# Arduino_lcd.net
KiCad netlist of a schematic drawn in EAGLE
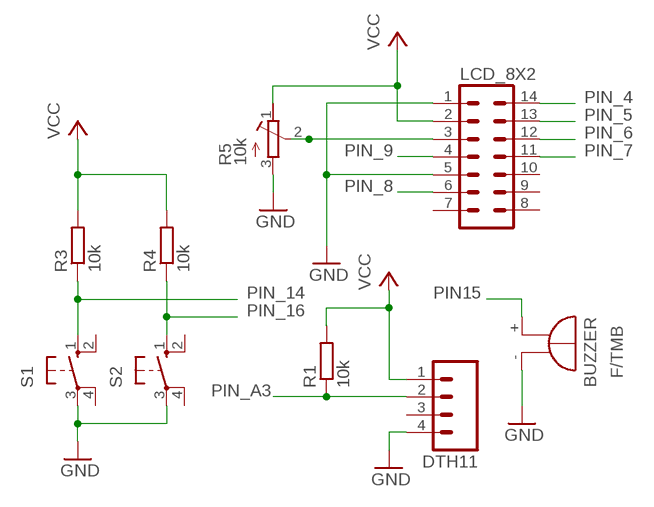
[diagram p0: schematic, sheet 1]

(export (version "E")
  (design (tool "Eeschema 10.0.6"))
  (components
    (comp (ref "BUZZER")
      (value "F/TMB")
      (footprint "eagle-import:F_TMB")
      (libsource (lib "eagle-import") (part "F/TMB"))
    )
    (comp (ref "DTH11")
      (value "M04")
      (footprint "eagle-import:04P")
      (libsource (lib "eagle-import") (part "M04"))
    )
    (comp (ref "LCD_8X2")
      (value "IC14P")
      (footprint "eagle-import:IC14P")
      (libsource (lib "eagle-import") (part "IC14P"))
    )
    (comp (ref "R1")
      (value "10k")
      (footprint "eagle-import:0207_10")
      (libsource (lib "eagle-import") (part "R-EU_0207/10"))
    )
    (comp (ref "R3")
      (value "10k")
      (footprint "eagle-import:0207_10")
      (libsource (lib "eagle-import") (part "R-EU_0207/10"))
    )
    (comp (ref "R4")
      (value "10k")
      (footprint "eagle-import:0207_10")
      (libsource (lib "eagle-import") (part "R-EU_0207/10"))
    )
    (comp (ref "R5")
      (value "10k")
      (footprint "eagle-import:RTRIM3314J")
      (libsource (lib "eagle-import") (part "R-TRIMM3314J"))
    )
    (comp (ref "S1")
      (value "10-XX")
      (footprint "eagle-import:B3F-10XX")
      (fields (field (name "MPN") "B3F-1000"))
      (libsource (lib "eagle-import") (part "10-XX"))
    )
    (comp (ref "S2")
      (value "10-XX")
      (footprint "eagle-import:B3F-10XX")
      (fields (field (name "MPN") "B3F-1000"))
      (libsource (lib "eagle-import") (part "10-XX"))
    )
  )
  (nets
    (net (code "1") (name "/PIN15") (class "Default")
      (node (ref "BUZZER") (pin "+") (pinfunction "+_+") (pintype "passive"))
    )
    (net (code "2") (name "/PIN_4") (class "Default")
      (node (ref "LCD_8X2") (pin "14") (pinfunction "14_14") (pintype "passive"))
    )
    (net (code "3") (name "/PIN_5") (class "Default")
      (node (ref "LCD_8X2") (pin "13") (pinfunction "13_13") (pintype "passive"))
    )
    (net (code "4") (name "/PIN_6") (class "Default")
      (node (ref "LCD_8X2") (pin "12") (pinfunction "12_12") (pintype "passive"))
    )
    (net (code "5") (name "/PIN_7") (class "Default")
      (node (ref "LCD_8X2") (pin "11") (pinfunction "11_11") (pintype "passive"))
    )
    (net (code "6") (name "/PIN_8") (class "Default")
      (node (ref "LCD_8X2") (pin "6") (pinfunction "6_6") (pintype "passive"))
    )
    (net (code "7") (name "/PIN_9") (class "Default")
      (node (ref "LCD_8X2") (pin "4") (pinfunction "4_4") (pintype "passive"))
    )
    (net (code "8") (name "/PIN_14") (class "Default")
      (node (ref "R3") (pin "1") (pinfunction "1_1") (pintype "passive"))
      (node (ref "S1") (pin "1") (pinfunction "S_1") (pintype "passive"))
    )
    (net (code "9") (name "/PIN_16") (class "Default")
      (node (ref "R4") (pin "1") (pinfunction "1_1") (pintype "passive"))
      (node (ref "S2") (pin "1") (pinfunction "S_1") (pintype "passive"))
    )
    (net (code "10") (name "/PIN_A3") (class "Default")
      (node (ref "DTH11") (pin "2") (pinfunction "2_2") (pintype "passive"))
      (node (ref "R1") (pin "1") (pinfunction "1_1") (pintype "passive"))
    )
    (net (code "11") (name "GND") (class "Default")
      (node (ref "BUZZER") (pin "-") (pinfunction "-_-") (pintype "passive"))
      (node (ref "DTH11") (pin "4") (pinfunction "4_4") (pintype "passive"))
      (node (ref "LCD_8X2") (pin "1") (pinfunction "1_1") (pintype "passive"))
      (node (ref "LCD_8X2") (pin "5") (pinfunction "5_5") (pintype "passive"))
      (node (ref "R5") (pin "3") (pinfunction "A_3") (pintype "passive"))
      (node (ref "S1") (pin "3") (pinfunction "P_3") (pintype "passive"))
      (node (ref "S2") (pin "3") (pinfunction "P_3") (pintype "passive"))
    )
    (net (code "12") (name "Net-(R5-S)") (class "Default")
      (node (ref "LCD_8X2") (pin "3") (pinfunction "3_3") (pintype "passive"))
      (node (ref "R5") (pin "2") (pinfunction "S_2") (pintype "passive"))
    )
    (net (code "13") (name "VCC") (class "Default")
      (node (ref "DTH11") (pin "1") (pinfunction "1_1") (pintype "passive"))
      (node (ref "LCD_8X2") (pin "2") (pinfunction "2_2") (pintype "passive"))
      (node (ref "R1") (pin "2") (pinfunction "2_2") (pintype "passive"))
      (node (ref "R3") (pin "2") (pinfunction "2_2") (pintype "passive"))
      (node (ref "R4") (pin "2") (pinfunction "2_2") (pintype "passive"))
      (node (ref "R5") (pin "1") (pinfunction "E_1") (pintype "passive"))
    )
    (net (code "14") (name "unconnected-(DTH11-Pad3)") (class "Default")
      (node (ref "DTH11") (pin "3") (pinfunction "3_3") (pintype "passive"))
    )
    (net (code "15") (name "unconnected-(LCD_8X2-Pad7)") (class "Default")
      (node (ref "LCD_8X2") (pin "7") (pinfunction "7_7") (pintype "passive"))
    )
    (net (code "16") (name "unconnected-(LCD_8X2-Pad8)") (class "Default")
      (node (ref "LCD_8X2") (pin "8") (pinfunction "8_8") (pintype "passive"))
    )
    (net (code "17") (name "unconnected-(LCD_8X2-Pad9)") (class "Default")
      (node (ref "LCD_8X2") (pin "9") (pinfunction "9_9") (pintype "passive"))
    )
    (net (code "18") (name "unconnected-(LCD_8X2-Pad10)") (class "Default")
      (node (ref "LCD_8X2") (pin "10") (pinfunction "10_10") (pintype "passive"))
    )
    (net (code "19") (name "unconnected-(S1-P1-Pad4)") (class "Default")
      (node (ref "S1") (pin "4") (pinfunction "P1_4") (pintype "passive"))
    )
    (net (code "20") (name "unconnected-(S1-S1-Pad2)") (class "Default")
      (node (ref "S1") (pin "2") (pinfunction "S1_2") (pintype "passive"))
    )
    (net (code "21") (name "unconnected-(S2-P1-Pad4)") (class "Default")
      (node (ref "S2") (pin "4") (pinfunction "P1_4") (pintype "passive"))
    )
    (net (code "22") (name "unconnected-(S2-S1-Pad2)") (class "Default")
      (node (ref "S2") (pin "2") (pinfunction "S1_2") (pintype "passive"))
    )
  )
)
